# control_board.net
KiCad netlist of a schematic drawn in EAGLE
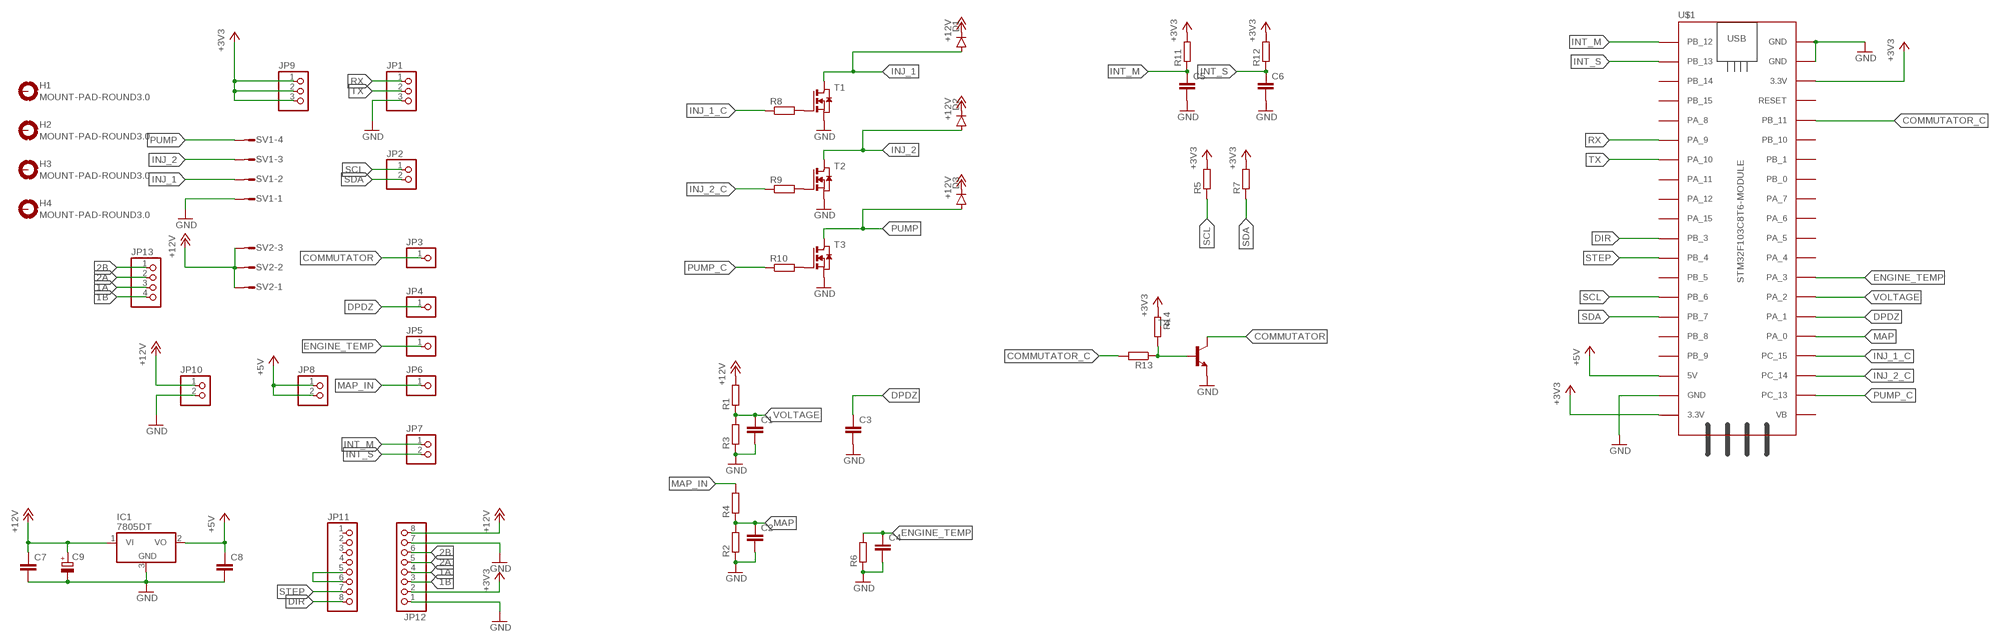
[diagram p0: schematic, sheet 1]

(export (version "E")
  (design (tool "Eeschema 10.0.6"))
  (components
    (comp (ref "C1")
      (value "C-EUC1206")
      (footprint "eagle-import:C1206")
      (libsource (lib "eagle-import") (part "C-EUC1206"))
    )
    (comp (ref "C2")
      (value "C-EUC1206")
      (footprint "eagle-import:C1206")
      (libsource (lib "eagle-import") (part "C-EUC1206"))
    )
    (comp (ref "C3")
      (value "C-EUC1206")
      (footprint "eagle-import:C1206")
      (libsource (lib "eagle-import") (part "C-EUC1206"))
    )
    (comp (ref "C4")
      (value "C-EUC1206")
      (footprint "eagle-import:C1206")
      (libsource (lib "eagle-import") (part "C-EUC1206"))
    )
    (comp (ref "C5")
      (value "C-EUC1206")
      (footprint "eagle-import:C1206")
      (libsource (lib "eagle-import") (part "C-EUC1206"))
    )
    (comp (ref "C6")
      (value "C-EUC1206")
      (footprint "eagle-import:C1206")
      (libsource (lib "eagle-import") (part "C-EUC1206"))
    )
    (comp (ref "C7")
      (value "C-EUC1206")
      (footprint "eagle-import:C1206")
      (libsource (lib "eagle-import") (part "C-EUC1206"))
    )
    (comp (ref "C8")
      (value "C-EUC1206")
      (footprint "eagle-import:C1206")
      (libsource (lib "eagle-import") (part "C-EUC1206"))
    )
    (comp (ref "C9")
      (value "CPOL-EU140CLH-0810")
      (footprint "eagle-import:140CLH-0810")
      (libsource (lib "eagle-import") (part "CPOL-EU140CLH-0810"))
    )
    (comp (ref "D1")
      (value "DIODE-SMB")
      (footprint "eagle-import:SMB")
      (libsource (lib "eagle-import") (part "DIODE-SMB"))
    )
    (comp (ref "D2")
      (value "DIODE-SMB")
      (footprint "eagle-import:SMB")
      (libsource (lib "eagle-import") (part "DIODE-SMB"))
    )
    (comp (ref "D3")
      (value "DIODE-SMB")
      (footprint "eagle-import:SMB")
      (libsource (lib "eagle-import") (part "DIODE-SMB"))
    )
    (comp (ref "H1")
      (value "MOUNT-PAD-ROUND3.0")
      (footprint "eagle-import:3,0-PAD")
      (libsource (lib "eagle-import") (part "MOUNT-PAD-ROUND3.0"))
    )
    (comp (ref "H2")
      (value "MOUNT-PAD-ROUND3.0")
      (footprint "eagle-import:3,0-PAD")
      (libsource (lib "eagle-import") (part "MOUNT-PAD-ROUND3.0"))
    )
    (comp (ref "H3")
      (value "MOUNT-PAD-ROUND3.0")
      (footprint "eagle-import:3,0-PAD")
      (libsource (lib "eagle-import") (part "MOUNT-PAD-ROUND3.0"))
    )
    (comp (ref "H4")
      (value "MOUNT-PAD-ROUND3.0")
      (footprint "eagle-import:3,0-PAD")
      (libsource (lib "eagle-import") (part "MOUNT-PAD-ROUND3.0"))
    )
    (comp (ref "IC1")
      (value "7805DT")
      (footprint "eagle-import:TO252")
      (libsource (lib "eagle-import") (part "78DT05"))
    )
    (comp (ref "JP1")
      (value "PINHD-1X3")
      (footprint "eagle-import:1X03")
      (libsource (lib "eagle-import") (part "PINHD-1X3"))
    )
    (comp (ref "JP2")
      (value "PINHD-1X2")
      (footprint "eagle-import:1X02")
      (libsource (lib "eagle-import") (part "PINHD-1X2"))
    )
    (comp (ref "JP3")
      (value "PINHD-1X1")
      (footprint "eagle-import:1X01")
      (libsource (lib "eagle-import") (part "PINHD-1X1"))
    )
    (comp (ref "JP4")
      (value "PINHD-1X1")
      (footprint "eagle-import:1X01")
      (libsource (lib "eagle-import") (part "PINHD-1X1"))
    )
    (comp (ref "JP5")
      (value "PINHD-1X1")
      (footprint "eagle-import:1X01")
      (libsource (lib "eagle-import") (part "PINHD-1X1"))
    )
    (comp (ref "JP6")
      (value "PINHD-1X1")
      (footprint "eagle-import:1X01")
      (libsource (lib "eagle-import") (part "PINHD-1X1"))
    )
    (comp (ref "JP7")
      (value "PINHD-1X2")
      (footprint "eagle-import:1X02")
      (libsource (lib "eagle-import") (part "PINHD-1X2"))
    )
    (comp (ref "JP8")
      (value "PINHD-1X2")
      (footprint "eagle-import:1X02")
      (libsource (lib "eagle-import") (part "PINHD-1X2"))
    )
    (comp (ref "JP9")
      (value "PINHD-1X3")
      (footprint "eagle-import:1X03")
      (libsource (lib "eagle-import") (part "PINHD-1X3"))
    )
    (comp (ref "JP10")
      (value "PINHD-1X2")
      (footprint "eagle-import:1X02")
      (libsource (lib "eagle-import") (part "PINHD-1X2"))
    )
    (comp (ref "JP11")
      (value "PINHD-1X8")
      (footprint "eagle-import:1X08")
      (libsource (lib "eagle-import") (part "PINHD-1X8"))
    )
    (comp (ref "JP12")
      (value "PINHD-1X8")
      (footprint "eagle-import:1X08")
      (libsource (lib "eagle-import") (part "PINHD-1X8"))
    )
    (comp (ref "JP13")
      (value "PINHD-1X4")
      (footprint "eagle-import:1X04")
      (libsource (lib "eagle-import") (part "PINHD-1X4"))
    )
    (comp (ref "R1")
      (value "R-EU_R1206")
      (footprint "eagle-import:R1206")
      (libsource (lib "eagle-import") (part "R-EU_R1206"))
    )
    (comp (ref "R2")
      (value "R-EU_R1206")
      (footprint "eagle-import:R1206")
      (libsource (lib "eagle-import") (part "R-EU_R1206"))
    )
    (comp (ref "R3")
      (value "R-EU_R1206")
      (footprint "eagle-import:R1206")
      (libsource (lib "eagle-import") (part "R-EU_R1206"))
    )
    (comp (ref "R4")
      (value "R-EU_R1206")
      (footprint "eagle-import:R1206")
      (libsource (lib "eagle-import") (part "R-EU_R1206"))
    )
    (comp (ref "R5")
      (value "R-EU_R1206")
      (footprint "eagle-import:R1206")
      (libsource (lib "eagle-import") (part "R-EU_R1206"))
    )
    (comp (ref "R6")
      (value "R-EU_R1206")
      (footprint "eagle-import:R1206")
      (libsource (lib "eagle-import") (part "R-EU_R1206"))
    )
    (comp (ref "R7")
      (value "R-EU_R1206")
      (footprint "eagle-import:R1206")
      (libsource (lib "eagle-import") (part "R-EU_R1206"))
    )
    (comp (ref "R8")
      (value "R-EU_R0805")
      (footprint "eagle-import:R0805")
      (libsource (lib "eagle-import") (part "R-EU_R0805"))
    )
    (comp (ref "R9")
      (value "R-EU_R0805")
      (footprint "eagle-import:R0805")
      (libsource (lib "eagle-import") (part "R-EU_R0805"))
    )
    (comp (ref "R10")
      (value "R-EU_R0805")
      (footprint "eagle-import:R0805")
      (libsource (lib "eagle-import") (part "R-EU_R0805"))
    )
    (comp (ref "R11")
      (value "R-EU_R1206")
      (footprint "eagle-import:R1206")
      (libsource (lib "eagle-import") (part "R-EU_R1206"))
    )
    (comp (ref "R12")
      (value "R-EU_R1206")
      (footprint "eagle-import:R1206")
      (libsource (lib "eagle-import") (part "R-EU_R1206"))
    )
    (comp (ref "R13")
      (value "R-EU_R1206")
      (footprint "eagle-import:R1206")
      (libsource (lib "eagle-import") (part "R-EU_R1206"))
    )
    (comp (ref "R14")
      (value "R-EU_R1206")
      (footprint "eagle-import:R1206")
      (libsource (lib "eagle-import") (part "R-EU_R1206"))
    )
    (comp (ref "SV1")
      (value "MT6-4")
      (footprint "eagle-import:MT6-4")
      (libsource (lib "eagle-import") (part "MT6-4"))
    )
    (comp (ref "SV2")
      (value "MT6-3")
      (footprint "eagle-import:MT6-3")
      (libsource (lib "eagle-import") (part "MT6-3"))
    )
    (comp (ref "T1")
      (value "NMOSSOT223")
      (footprint "eagle-import:SOT223")
      (libsource (lib "eagle-import") (part "NMOSSOT223"))
    )
    (comp (ref "T2")
      (value "NMOSSOT223")
      (footprint "eagle-import:SOT223")
      (libsource (lib "eagle-import") (part "NMOSSOT223"))
    )
    (comp (ref "T3")
      (value "NMOSSOT223")
      (footprint "eagle-import:SOT223")
      (libsource (lib "eagle-import") (part "NMOSSOT223"))
    )
    (comp (ref "T4")
      (value "BCX54-NPN-SOT89-BCE")
      (footprint "eagle-import:SOT89-BCE")
      (libsource (lib "eagle-import") (part "-NPN-SOT89-BCEBCX54"))
    )
    (comp (ref "U$1")
      (value "STM32F103C8T6-MODULE")
      (footprint "eagle-import:STM32F103C8T6-MODULE")
      (libsource (lib "eagle-import") (part "STM32F103C8T6-MODULE"))
    )
  )
  (nets
    (net (code "1") (name "+3V3") (class "Default")
      (node (ref "JP12") (pin "2") (pinfunction "2_2") (pintype "passive"))
      (node (ref "JP9") (pin "1") (pinfunction "1_1") (pintype "passive"))
      (node (ref "JP9") (pin "2") (pinfunction "2_2") (pintype "passive"))
      (node (ref "JP9") (pin "3") (pinfunction "3_3") (pintype "passive"))
      (node (ref "R11") (pin "2") (pinfunction "2_2") (pintype "passive"))
      (node (ref "R12") (pin "2") (pinfunction "2_2") (pintype "passive"))
      (node (ref "R14") (pin "1") (pinfunction "1_1") (pintype "passive"))
      (node (ref "R5") (pin "2") (pinfunction "2_2") (pintype "passive"))
      (node (ref "R7") (pin "2") (pinfunction "2_2") (pintype "passive"))
      (node (ref "U$1") (pin "3.3V_1") (pinfunction "3.3V_3.3V_1") (pintype "bidirectional"))
      (node (ref "U$1") (pin "3.3V_2") (pinfunction "3.3V_3.3V_2") (pintype "bidirectional"))
    )
    (net (code "2") (name "+5V") (class "Default")
      (node (ref "C8") (pin "1") (pinfunction "1_1") (pintype "passive"))
      (node (ref "IC1") (pin "2") (pinfunction "VO_2") (pintype "passive"))
      (node (ref "JP8") (pin "1") (pinfunction "1_1") (pintype "passive"))
      (node (ref "JP8") (pin "2") (pinfunction "2_2") (pintype "passive"))
      (node (ref "U$1") (pin "5V") (pinfunction "5V_5V") (pintype "bidirectional"))
    )
    (net (code "3") (name "+12V") (class "Default")
      (node (ref "C7") (pin "1") (pinfunction "1_1") (pintype "passive"))
      (node (ref "C9") (pin "+") (pinfunction "+_+") (pintype "passive"))
      (node (ref "D1") (pin "C") (pinfunction "C_C") (pintype "passive"))
      (node (ref "D2") (pin "C") (pinfunction "C_C") (pintype "passive"))
      (node (ref "D3") (pin "C") (pinfunction "C_C") (pintype "passive"))
      (node (ref "IC1") (pin "1") (pinfunction "VI_1") (pintype "input"))
      (node (ref "JP10") (pin "1") (pinfunction "1_1") (pintype "passive"))
      (node (ref "JP12") (pin "8") (pinfunction "8_8") (pintype "passive"))
      (node (ref "R1") (pin "2") (pinfunction "2_2") (pintype "passive"))
      (node (ref "SV2") (pin "1") (pinfunction "S_1") (pintype "passive"))
      (node (ref "SV2") (pin "2") (pinfunction "S_2") (pintype "passive"))
      (node (ref "SV2") (pin "3") (pinfunction "S_3") (pintype "passive"))
    )
    (net (code "4") (name "1A") (class "Default")
      (node (ref "JP12") (pin "4") (pinfunction "4_4") (pintype "passive"))
      (node (ref "JP13") (pin "3") (pinfunction "3_3") (pintype "passive"))
    )
    (net (code "5") (name "1B") (class "Default")
      (node (ref "JP12") (pin "3") (pinfunction "3_3") (pintype "passive"))
      (node (ref "JP13") (pin "4") (pinfunction "4_4") (pintype "passive"))
    )
    (net (code "6") (name "2A") (class "Default")
      (node (ref "JP12") (pin "5") (pinfunction "5_5") (pintype "passive"))
      (node (ref "JP13") (pin "2") (pinfunction "2_2") (pintype "passive"))
    )
    (net (code "7") (name "2B") (class "Default")
      (node (ref "JP12") (pin "6") (pinfunction "6_6") (pintype "passive"))
      (node (ref "JP13") (pin "1") (pinfunction "1_1") (pintype "passive"))
    )
    (net (code "8") (name "COMMUTATOR") (class "Default")
      (node (ref "JP3") (pin "1") (pinfunction "1_1") (pintype "passive"))
      (node (ref "T4") (pin "C") (pinfunction "C_C") (pintype "passive"))
    )
    (net (code "9") (name "COMMUTATOR_C") (class "Default")
      (node (ref "R13") (pin "2") (pinfunction "2_2") (pintype "passive"))
      (node (ref "U$1") (pin "PB_11") (pinfunction "PB_11_PB_11") (pintype "bidirectional"))
    )
    (net (code "10") (name "DIR") (class "Default")
      (node (ref "JP11") (pin "8") (pinfunction "8_8") (pintype "passive"))
      (node (ref "U$1") (pin "PB_3") (pinfunction "PB_3_PB_3") (pintype "bidirectional"))
    )
    (net (code "11") (name "DPDZ") (class "Default")
      (node (ref "C3") (pin "1") (pinfunction "1_1") (pintype "passive"))
      (node (ref "JP4") (pin "1") (pinfunction "1_1") (pintype "passive"))
      (node (ref "U$1") (pin "PA_1") (pinfunction "PA_1_PA_1") (pintype "bidirectional"))
    )
    (net (code "12") (name "ENGINE_TEMP") (class "Default")
      (node (ref "C4") (pin "1") (pinfunction "1_1") (pintype "passive"))
      (node (ref "JP5") (pin "1") (pinfunction "1_1") (pintype "passive"))
      (node (ref "R6") (pin "2") (pinfunction "2_2") (pintype "passive"))
      (node (ref "U$1") (pin "PA_3") (pinfunction "PA_3_PA_3") (pintype "bidirectional"))
    )
    (net (code "13") (name "GND") (class "Default")
      (node (ref "C1") (pin "2") (pinfunction "2_2") (pintype "passive"))
      (node (ref "C2") (pin "2") (pinfunction "2_2") (pintype "passive"))
      (node (ref "C3") (pin "2") (pinfunction "2_2") (pintype "passive"))
      (node (ref "C4") (pin "2") (pinfunction "2_2") (pintype "passive"))
      (node (ref "C5") (pin "2") (pinfunction "2_2") (pintype "passive"))
      (node (ref "C6") (pin "2") (pinfunction "2_2") (pintype "passive"))
      (node (ref "C7") (pin "2") (pinfunction "2_2") (pintype "passive"))
      (node (ref "C8") (pin "2") (pinfunction "2_2") (pintype "passive"))
      (node (ref "C9") (pin "-") (pinfunction "-_-") (pintype "passive"))
      (node (ref "IC1") (pin "3") (pinfunction "GND_3") (pintype "passive"))
      (node (ref "JP1") (pin "3") (pinfunction "3_3") (pintype "passive"))
      (node (ref "JP10") (pin "2") (pinfunction "2_2") (pintype "passive"))
      (node (ref "JP12") (pin "1") (pinfunction "1_1") (pintype "passive"))
      (node (ref "JP12") (pin "7") (pinfunction "7_7") (pintype "passive"))
      (node (ref "R2") (pin "1") (pinfunction "1_1") (pintype "passive"))
      (node (ref "R3") (pin "1") (pinfunction "1_1") (pintype "passive"))
      (node (ref "R6") (pin "1") (pinfunction "1_1") (pintype "passive"))
      (node (ref "SV1") (pin "1") (pinfunction "S_1") (pintype "passive"))
      (node (ref "T1") (pin "3") (pinfunction "S_3") (pintype "passive"))
      (node (ref "T2") (pin "3") (pinfunction "S_3") (pintype "passive"))
      (node (ref "T3") (pin "3") (pinfunction "S_3") (pintype "passive"))
      (node (ref "T4") (pin "E") (pinfunction "E_E") (pintype "passive"))
      (node (ref "U$1") (pin "GND_1") (pinfunction "GND_GND_1") (pintype "bidirectional"))
      (node (ref "U$1") (pin "GND_2") (pinfunction "GND_GND_2") (pintype "bidirectional"))
      (node (ref "U$1") (pin "GND_3") (pinfunction "GND_GND_3") (pintype "power_in"))
    )
    (net (code "14") (name "INJ_1") (class "Default")
      (node (ref "D1") (pin "A") (pinfunction "A_A") (pintype "passive"))
      (node (ref "SV1") (pin "2") (pinfunction "S_2") (pintype "passive"))
      (node (ref "T1") (pin "2") (pinfunction "D_2") (pintype "passive"))
      (node (ref "T1") (pin "4") (pinfunction "D_4") (pintype "passive"))
    )
    (net (code "15") (name "INJ_1_C") (class "Default")
      (node (ref "R8") (pin "1") (pinfunction "1_1") (pintype "passive"))
      (node (ref "U$1") (pin "PC_15") (pinfunction "PC_15_PC_15") (pintype "bidirectional"))
    )
    (net (code "16") (name "INJ_2") (class "Default")
      (node (ref "D2") (pin "A") (pinfunction "A_A") (pintype "passive"))
      (node (ref "SV1") (pin "3") (pinfunction "S_3") (pintype "passive"))
      (node (ref "T2") (pin "2") (pinfunction "D_2") (pintype "passive"))
      (node (ref "T2") (pin "4") (pinfunction "D_4") (pintype "passive"))
    )
    (net (code "17") (name "INJ_2_C") (class "Default")
      (node (ref "R9") (pin "1") (pinfunction "1_1") (pintype "passive"))
      (node (ref "U$1") (pin "PC_14") (pinfunction "PC_14_PC_14") (pintype "bidirectional"))
    )
    (net (code "18") (name "INT_M") (class "Default")
      (node (ref "C5") (pin "1") (pinfunction "1_1") (pintype "passive"))
      (node (ref "JP7") (pin "1") (pinfunction "1_1") (pintype "passive"))
      (node (ref "R11") (pin "1") (pinfunction "1_1") (pintype "passive"))
      (node (ref "U$1") (pin "PB_12") (pinfunction "PB_12_PB_12") (pintype "bidirectional"))
    )
    (net (code "19") (name "INT_S") (class "Default")
      (node (ref "C6") (pin "1") (pinfunction "1_1") (pintype "passive"))
      (node (ref "JP7") (pin "2") (pinfunction "2_2") (pintype "passive"))
      (node (ref "R12") (pin "1") (pinfunction "1_1") (pintype "passive"))
      (node (ref "U$1") (pin "PB_13") (pinfunction "PB_13_PB_13") (pintype "bidirectional"))
    )
    (net (code "20") (name "MAP") (class "Default")
      (node (ref "C2") (pin "1") (pinfunction "1_1") (pintype "passive"))
      (node (ref "R2") (pin "2") (pinfunction "2_2") (pintype "passive"))
      (node (ref "R4") (pin "1") (pinfunction "1_1") (pintype "passive"))
      (node (ref "U$1") (pin "PA_0") (pinfunction "PA_0_PA_0") (pintype "bidirectional"))
    )
    (net (code "21") (name "MAP_IN") (class "Default")
      (node (ref "JP6") (pin "1") (pinfunction "1_1") (pintype "passive"))
      (node (ref "R4") (pin "2") (pinfunction "2_2") (pintype "passive"))
    )
    (net (code "22") (name "Net-(JP11-Pad5)") (class "Default")
      (node (ref "JP11") (pin "5") (pinfunction "5_5") (pintype "passive"))
      (node (ref "JP11") (pin "6") (pinfunction "6_6") (pintype "passive"))
    )
    (net (code "23") (name "Net-(R13-Pad1)") (class "Default")
      (node (ref "R13") (pin "1") (pinfunction "1_1") (pintype "passive"))
      (node (ref "R14") (pin "2") (pinfunction "2_2") (pintype "passive"))
      (node (ref "T4") (pin "B") (pinfunction "B_B") (pintype "passive"))
    )
    (net (code "24") (name "Net-(T1-G)") (class "Default")
      (node (ref "R8") (pin "2") (pinfunction "2_2") (pintype "passive"))
      (node (ref "T1") (pin "1") (pinfunction "G_1") (pintype "passive"))
    )
    (net (code "25") (name "Net-(T2-G)") (class "Default")
      (node (ref "R9") (pin "2") (pinfunction "2_2") (pintype "passive"))
      (node (ref "T2") (pin "1") (pinfunction "G_1") (pintype "passive"))
    )
    (net (code "26") (name "Net-(T3-G)") (class "Default")
      (node (ref "R10") (pin "2") (pinfunction "2_2") (pintype "passive"))
      (node (ref "T3") (pin "1") (pinfunction "G_1") (pintype "passive"))
    )
    (net (code "27") (name "PUMP") (class "Default")
      (node (ref "D3") (pin "A") (pinfunction "A_A") (pintype "passive"))
      (node (ref "SV1") (pin "4") (pinfunction "S_4") (pintype "passive"))
      (node (ref "T3") (pin "2") (pinfunction "D_2") (pintype "passive"))
      (node (ref "T3") (pin "4") (pinfunction "D_4") (pintype "passive"))
    )
    (net (code "28") (name "PUMP_C") (class "Default")
      (node (ref "R10") (pin "1") (pinfunction "1_1") (pintype "passive"))
      (node (ref "U$1") (pin "PC_13") (pinfunction "PC_13_PC_13") (pintype "bidirectional"))
    )
    (net (code "29") (name "RX") (class "Default")
      (node (ref "JP1") (pin "1") (pinfunction "1_1") (pintype "passive"))
      (node (ref "U$1") (pin "PA_9") (pinfunction "PA_9_PA_9") (pintype "bidirectional"))
    )
    (net (code "30") (name "SCL") (class "Default")
      (node (ref "JP2") (pin "1") (pinfunction "1_1") (pintype "passive"))
      (node (ref "R5") (pin "1") (pinfunction "1_1") (pintype "passive"))
      (node (ref "U$1") (pin "PB_6") (pinfunction "PB_6_PB_6") (pintype "bidirectional"))
    )
    (net (code "31") (name "SDA") (class "Default")
      (node (ref "JP2") (pin "2") (pinfunction "2_2") (pintype "passive"))
      (node (ref "R7") (pin "1") (pinfunction "1_1") (pintype "passive"))
      (node (ref "U$1") (pin "PB_7") (pinfunction "PB_7_PB_7") (pintype "bidirectional"))
    )
    (net (code "32") (name "STEP") (class "Default")
      (node (ref "JP11") (pin "7") (pinfunction "7_7") (pintype "passive"))
      (node (ref "U$1") (pin "PB_4") (pinfunction "PB_4_PB_4") (pintype "bidirectional"))
    )
    (net (code "33") (name "TX") (class "Default")
      (node (ref "JP1") (pin "2") (pinfunction "2_2") (pintype "passive"))
      (node (ref "U$1") (pin "PA_10") (pinfunction "PA_10_PA_10") (pintype "bidirectional"))
    )
    (net (code "34") (name "VOLTAGE") (class "Default")
      (node (ref "C1") (pin "1") (pinfunction "1_1") (pintype "passive"))
      (node (ref "R1") (pin "1") (pinfunction "1_1") (pintype "passive"))
      (node (ref "R3") (pin "2") (pinfunction "2_2") (pintype "passive"))
      (node (ref "U$1") (pin "PA_2") (pinfunction "PA_2_PA_2") (pintype "bidirectional"))
    )
    (net (code "35") (name "unconnected-(H1-MOUNT-PadB3,0)") (class "Default")
      (node (ref "H1") (pin "B3,0") (pinfunction "MOUNT_B3,0") (pintype "passive"))
    )
    (net (code "36") (name "unconnected-(H2-MOUNT-PadB3,0)") (class "Default")
      (node (ref "H2") (pin "B3,0") (pinfunction "MOUNT_B3,0") (pintype "passive"))
    )
    (net (code "37") (name "unconnected-(H3-MOUNT-PadB3,0)") (class "Default")
      (node (ref "H3") (pin "B3,0") (pinfunction "MOUNT_B3,0") (pintype "passive"))
    )
    (net (code "38") (name "unconnected-(H4-MOUNT-PadB3,0)") (class "Default")
      (node (ref "H4") (pin "B3,0") (pinfunction "MOUNT_B3,0") (pintype "passive"))
    )
    (net (code "39") (name "unconnected-(JP11-Pad1)") (class "Default")
      (node (ref "JP11") (pin "1") (pinfunction "1_1") (pintype "passive"))
    )
    (net (code "40") (name "unconnected-(JP11-Pad2)") (class "Default")
      (node (ref "JP11") (pin "2") (pinfunction "2_2") (pintype "passive"))
    )
    (net (code "41") (name "unconnected-(JP11-Pad3)") (class "Default")
      (node (ref "JP11") (pin "3") (pinfunction "3_3") (pintype "passive"))
    )
    (net (code "42") (name "unconnected-(JP11-Pad4)") (class "Default")
      (node (ref "JP11") (pin "4") (pinfunction "4_4") (pintype "passive"))
    )
    (net (code "43") (name "unconnected-(U$1-PadPA_4)") (class "Default")
      (node (ref "U$1") (pin "PA_4") (pinfunction "PA_4_PA_4") (pintype "bidirectional"))
    )
    (net (code "44") (name "unconnected-(U$1-PadPA_5)") (class "Default")
      (node (ref "U$1") (pin "PA_5") (pinfunction "PA_5_PA_5") (pintype "bidirectional"))
    )
    (net (code "45") (name "unconnected-(U$1-PadPA_6)") (class "Default")
      (node (ref "U$1") (pin "PA_6") (pinfunction "PA_6_PA_6") (pintype "bidirectional"))
    )
    (net (code "46") (name "unconnected-(U$1-PadPA_7)") (class "Default")
      (node (ref "U$1") (pin "PA_7") (pinfunction "PA_7_PA_7") (pintype "bidirectional"))
    )
    (net (code "47") (name "unconnected-(U$1-PadPA_8)") (class "Default")
      (node (ref "U$1") (pin "PA_8") (pinfunction "PA_8_PA_8") (pintype "bidirectional"))
    )
    (net (code "48") (name "unconnected-(U$1-PadPA_11)") (class "Default")
      (node (ref "U$1") (pin "PA_11") (pinfunction "PA_11_PA_11") (pintype "bidirectional"))
    )
    (net (code "49") (name "unconnected-(U$1-PadPA_12)") (class "Default")
      (node (ref "U$1") (pin "PA_12") (pinfunction "PA_12_PA_12") (pintype "bidirectional"))
    )
    (net (code "50") (name "unconnected-(U$1-PadPA_15)") (class "Default")
      (node (ref "U$1") (pin "PA_15") (pinfunction "PA_15_PA_15") (pintype "bidirectional"))
    )
    (net (code "51") (name "unconnected-(U$1-PadPB_0)") (class "Default")
      (node (ref "U$1") (pin "PB_0") (pinfunction "PB_0_PB_0") (pintype "bidirectional"))
    )
    (net (code "52") (name "unconnected-(U$1-PadPB_1)") (class "Default")
      (node (ref "U$1") (pin "PB_1") (pinfunction "PB_1_PB_1") (pintype "bidirectional"))
    )
    (net (code "53") (name "unconnected-(U$1-PadPB_5)") (class "Default")
      (node (ref "U$1") (pin "PB_5") (pinfunction "PB_5_PB_5") (pintype "bidirectional"))
    )
    (net (code "54") (name "unconnected-(U$1-PadPB_8)") (class "Default")
      (node (ref "U$1") (pin "PB_8") (pinfunction "PB_8_PB_8") (pintype "bidirectional"))
    )
    (net (code "55") (name "unconnected-(U$1-PadPB_9)") (class "Default")
      (node (ref "U$1") (pin "PB_9") (pinfunction "PB_9_PB_9") (pintype "bidirectional"))
    )
    (net (code "56") (name "unconnected-(U$1-PadPB_10)") (class "Default")
      (node (ref "U$1") (pin "PB_10") (pinfunction "PB_10_PB_10") (pintype "bidirectional"))
    )
    (net (code "57") (name "unconnected-(U$1-PadPB_14)") (class "Default")
      (node (ref "U$1") (pin "PB_14") (pinfunction "PB_14_PB_14") (pintype "bidirectional"))
    )
    (net (code "58") (name "unconnected-(U$1-PadPB_15)") (class "Default")
      (node (ref "U$1") (pin "PB_15") (pinfunction "PB_15_PB_15") (pintype "bidirectional"))
    )
    (net (code "59") (name "unconnected-(U$1-PadRESET)") (class "Default")
      (node (ref "U$1") (pin "RESET") (pinfunction "RESET_RESET") (pintype "bidirectional"))
    )
    (net (code "60") (name "unconnected-(U$1-PadVB)") (class "Default")
      (node (ref "U$1") (pin "VB") (pinfunction "VB_VB") (pintype "bidirectional"))
    )
  )
)
